# HoneyPI_I2C_Extenter.net
KiCad netlist of a schematic drawn in EAGLE
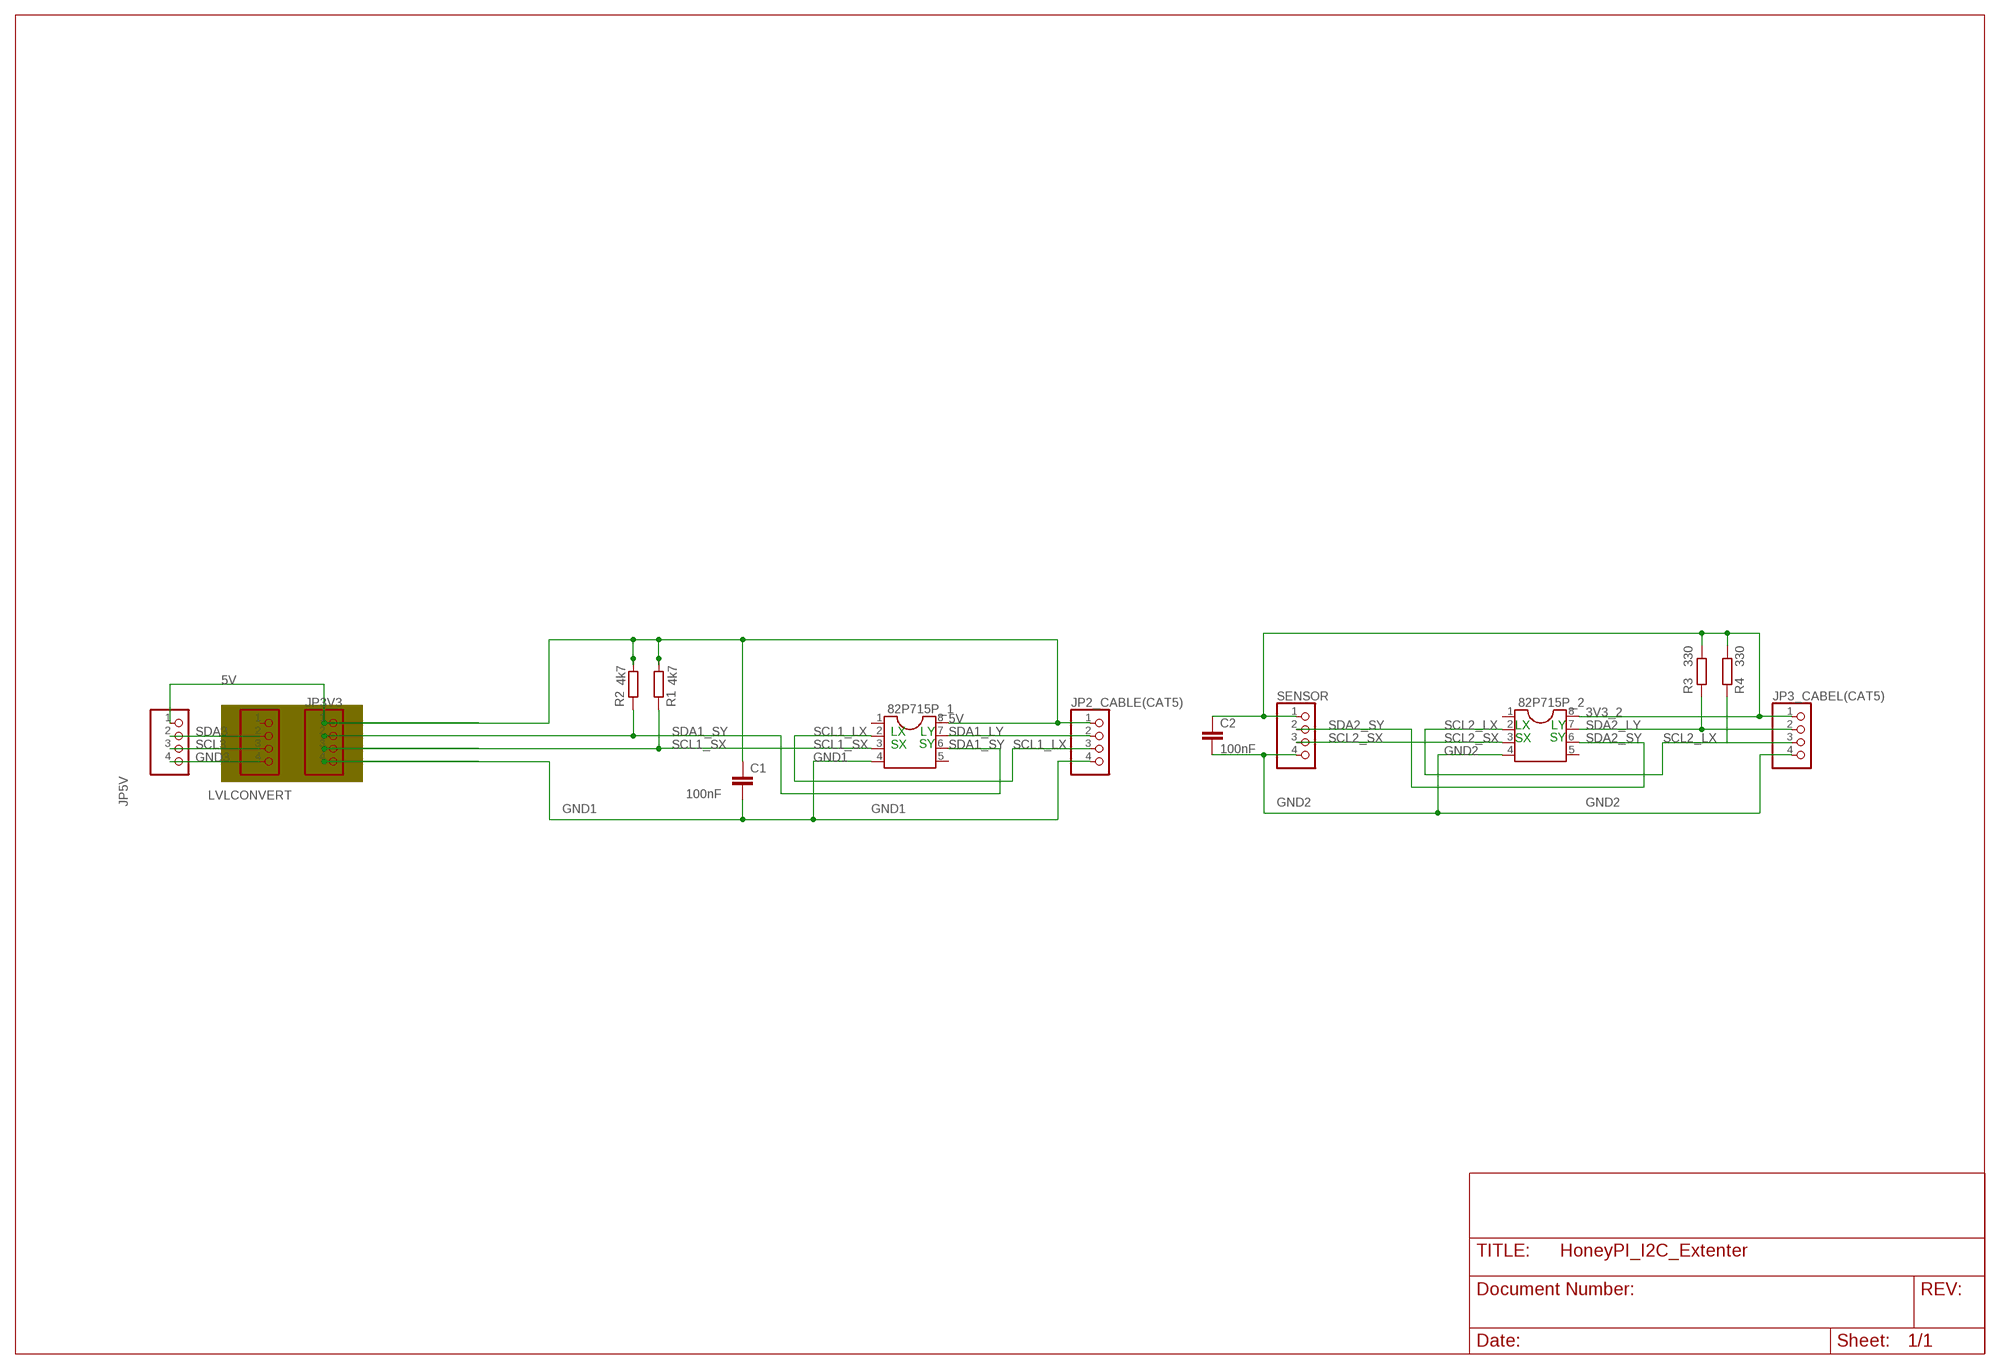
[diagram p0: schematic, sheet 1]

(export (version "E")
  (design (tool "Eeschema 10.0.6"))
  (components
    (comp (ref "82P715P_1")
      (value "DIL8")
      (footprint "eagle-import:DIL08")
      (libsource (lib "eagle-import") (part "DIL8"))
    )
    (comp (ref "82P715P_2")
      (value "DIL8")
      (footprint "eagle-import:DIL08")
      (libsource (lib "eagle-import") (part "DIL8"))
    )
    (comp (ref "C1")
      (value "100nF")
      (footprint "eagle-import:C050-045X075")
      (libsource (lib "eagle-import") (part "C-EU050-045X075"))
    )
    (comp (ref "C2")
      (value "100nF")
      (footprint "eagle-import:C050-045X075")
      (libsource (lib "eagle-import") (part "C-EU050-045X075"))
    )
    (comp (ref "JP2_CABLE(CAT5)")
      (value "PINHD-1X4")
      (footprint "eagle-import:1X04")
      (libsource (lib "eagle-import") (part "PINHD-1X4"))
    )
    (comp (ref "JP3V3")
      (value "PINHD-1X4")
      (footprint "eagle-import:1X04")
      (libsource (lib "eagle-import") (part "PINHD-1X4"))
    )
    (comp (ref "JP3_CABEL(CAT5)")
      (value "PINHD-1X4")
      (footprint "eagle-import:1X04")
      (libsource (lib "eagle-import") (part "PINHD-1X4"))
    )
    (comp (ref "JP5V")
      (value "PINHD-1X4")
      (footprint "eagle-import:1X04")
      (libsource (lib "eagle-import") (part "PINHD-1X4"))
    )
    (comp (ref "LVLCONVERT")
      (value "PINHD-1X4")
      (footprint "eagle-import:1X04")
      (libsource (lib "eagle-import") (part "PINHD-1X4"))
    )
    (comp (ref "R1")
      (value "4k7")
      (footprint "eagle-import:0207_7")
      (libsource (lib "eagle-import") (part "R-EU_0207/7"))
    )
    (comp (ref "R2")
      (value "4k7")
      (footprint "eagle-import:0207_7")
      (libsource (lib "eagle-import") (part "R-EU_0207/7"))
    )
    (comp (ref "R3")
      (value "330")
      (footprint "eagle-import:0207_7")
      (libsource (lib "eagle-import") (part "R-EU_0207/7"))
    )
    (comp (ref "R4")
      (value "330")
      (footprint "eagle-import:0207_7")
      (libsource (lib "eagle-import") (part "R-EU_0207/7"))
    )
    (comp (ref "SENSOR")
      (value "PINHD-1X4")
      (footprint "eagle-import:1X04")
      (libsource (lib "eagle-import") (part "PINHD-1X4"))
    )
  )
  (nets
    (net (code "1") (name "/3V3_2") (class "Default")
      (node (ref "82P715P_2") (pin "8") (pinfunction "8_8") (pintype "passive"))
      (node (ref "C2") (pin "1") (pinfunction "1_1") (pintype "passive"))
      (node (ref "JP3_CABEL(CAT5)") (pin "1") (pinfunction "1_1") (pintype "passive"))
      (node (ref "R3") (pin "1") (pinfunction "1_1") (pintype "passive"))
      (node (ref "R4") (pin "1") (pinfunction "1_1") (pintype "passive"))
      (node (ref "SENSOR") (pin "1") (pinfunction "1_1") (pintype "passive"))
    )
    (net (code "2") (name "/5V") (class "Default")
      (node (ref "82P715P_1") (pin "8") (pinfunction "8_8") (pintype "passive"))
      (node (ref "C1") (pin "1") (pinfunction "1_1") (pintype "passive"))
      (node (ref "JP2_CABLE(CAT5)") (pin "1") (pinfunction "1_1") (pintype "passive"))
      (node (ref "JP3V3") (pin "1") (pinfunction "1_1") (pintype "passive"))
      (node (ref "JP5V") (pin "1") (pinfunction "1_1") (pintype "passive"))
      (node (ref "R1") (pin "1") (pinfunction "1_1") (pintype "passive"))
      (node (ref "R2") (pin "1") (pinfunction "1_1") (pintype "passive"))
    )
    (net (code "3") (name "/GND1") (class "Default")
      (node (ref "82P715P_1") (pin "4") (pinfunction "4_4") (pintype "passive"))
      (node (ref "C1") (pin "2") (pinfunction "2_2") (pintype "passive"))
      (node (ref "JP2_CABLE(CAT5)") (pin "4") (pinfunction "4_4") (pintype "passive"))
      (node (ref "JP3V3") (pin "4") (pinfunction "4_4") (pintype "passive"))
    )
    (net (code "4") (name "/GND2") (class "Default")
      (node (ref "82P715P_2") (pin "4") (pinfunction "4_4") (pintype "passive"))
      (node (ref "C2") (pin "2") (pinfunction "2_2") (pintype "passive"))
      (node (ref "JP3_CABEL(CAT5)") (pin "4") (pinfunction "4_4") (pintype "passive"))
      (node (ref "SENSOR") (pin "4") (pinfunction "4_4") (pintype "passive"))
    )
    (net (code "5") (name "/GND3") (class "Default")
      (node (ref "JP5V") (pin "4") (pinfunction "4_4") (pintype "passive"))
      (node (ref "LVLCONVERT") (pin "4") (pinfunction "4_4") (pintype "passive"))
    )
    (net (code "6") (name "/SCL1_LX") (class "Default")
      (node (ref "82P715P_1") (pin "2") (pinfunction "2_2") (pintype "passive"))
      (node (ref "JP2_CABLE(CAT5)") (pin "3") (pinfunction "3_3") (pintype "passive"))
    )
    (net (code "7") (name "/SCL1_SX") (class "Default")
      (node (ref "82P715P_1") (pin "3") (pinfunction "3_3") (pintype "passive"))
      (node (ref "JP3V3") (pin "3") (pinfunction "3_3") (pintype "passive"))
      (node (ref "R1") (pin "2") (pinfunction "2_2") (pintype "passive"))
    )
    (net (code "8") (name "/SCL2_LX") (class "Default")
      (node (ref "82P715P_2") (pin "2") (pinfunction "2_2") (pintype "passive"))
      (node (ref "JP3_CABEL(CAT5)") (pin "3") (pinfunction "3_3") (pintype "passive"))
      (node (ref "R4") (pin "2") (pinfunction "2_2") (pintype "passive"))
    )
    (net (code "9") (name "/SCL2_SX") (class "Default")
      (node (ref "82P715P_2") (pin "3") (pinfunction "3_3") (pintype "passive"))
      (node (ref "SENSOR") (pin "3") (pinfunction "3_3") (pintype "passive"))
    )
    (net (code "10") (name "/SCL3") (class "Default")
      (node (ref "JP5V") (pin "3") (pinfunction "3_3") (pintype "passive"))
      (node (ref "LVLCONVERT") (pin "3") (pinfunction "3_3") (pintype "passive"))
    )
    (net (code "11") (name "/SDA1_LY") (class "Default")
      (node (ref "82P715P_1") (pin "7") (pinfunction "7_7") (pintype "passive"))
      (node (ref "JP2_CABLE(CAT5)") (pin "2") (pinfunction "2_2") (pintype "passive"))
    )
    (net (code "12") (name "/SDA1_SY") (class "Default")
      (node (ref "82P715P_1") (pin "6") (pinfunction "6_6") (pintype "passive"))
      (node (ref "JP3V3") (pin "2") (pinfunction "2_2") (pintype "passive"))
      (node (ref "R2") (pin "2") (pinfunction "2_2") (pintype "passive"))
    )
    (net (code "13") (name "/SDA2_LY") (class "Default")
      (node (ref "82P715P_2") (pin "7") (pinfunction "7_7") (pintype "passive"))
      (node (ref "JP3_CABEL(CAT5)") (pin "2") (pinfunction "2_2") (pintype "passive"))
      (node (ref "R3") (pin "2") (pinfunction "2_2") (pintype "passive"))
    )
    (net (code "14") (name "/SDA2_SY") (class "Default")
      (node (ref "82P715P_2") (pin "6") (pinfunction "6_6") (pintype "passive"))
      (node (ref "SENSOR") (pin "2") (pinfunction "2_2") (pintype "passive"))
    )
    (net (code "15") (name "/SDA3") (class "Default")
      (node (ref "JP5V") (pin "2") (pinfunction "2_2") (pintype "passive"))
      (node (ref "LVLCONVERT") (pin "2") (pinfunction "2_2") (pintype "passive"))
    )
    (net (code "16") (name "unconnected-(82P715P_1-Pad1)") (class "Default")
      (node (ref "82P715P_1") (pin "1") (pinfunction "1_1") (pintype "passive"))
    )
    (net (code "17") (name "unconnected-(82P715P_1-Pad5)") (class "Default")
      (node (ref "82P715P_1") (pin "5") (pinfunction "5_5") (pintype "passive"))
    )
    (net (code "18") (name "unconnected-(82P715P_2-Pad1)") (class "Default")
      (node (ref "82P715P_2") (pin "1") (pinfunction "1_1") (pintype "passive"))
    )
    (net (code "19") (name "unconnected-(82P715P_2-Pad5)") (class "Default")
      (node (ref "82P715P_2") (pin "5") (pinfunction "5_5") (pintype "passive"))
    )
    (net (code "20") (name "unconnected-(LVLCONVERT-Pad1)") (class "Default")
      (node (ref "LVLCONVERT") (pin "1") (pinfunction "1_1") (pintype "passive"))
    )
  )
)
